# ESP_Thermometer.net
KiCad netlist of a schematic drawn in EAGLE
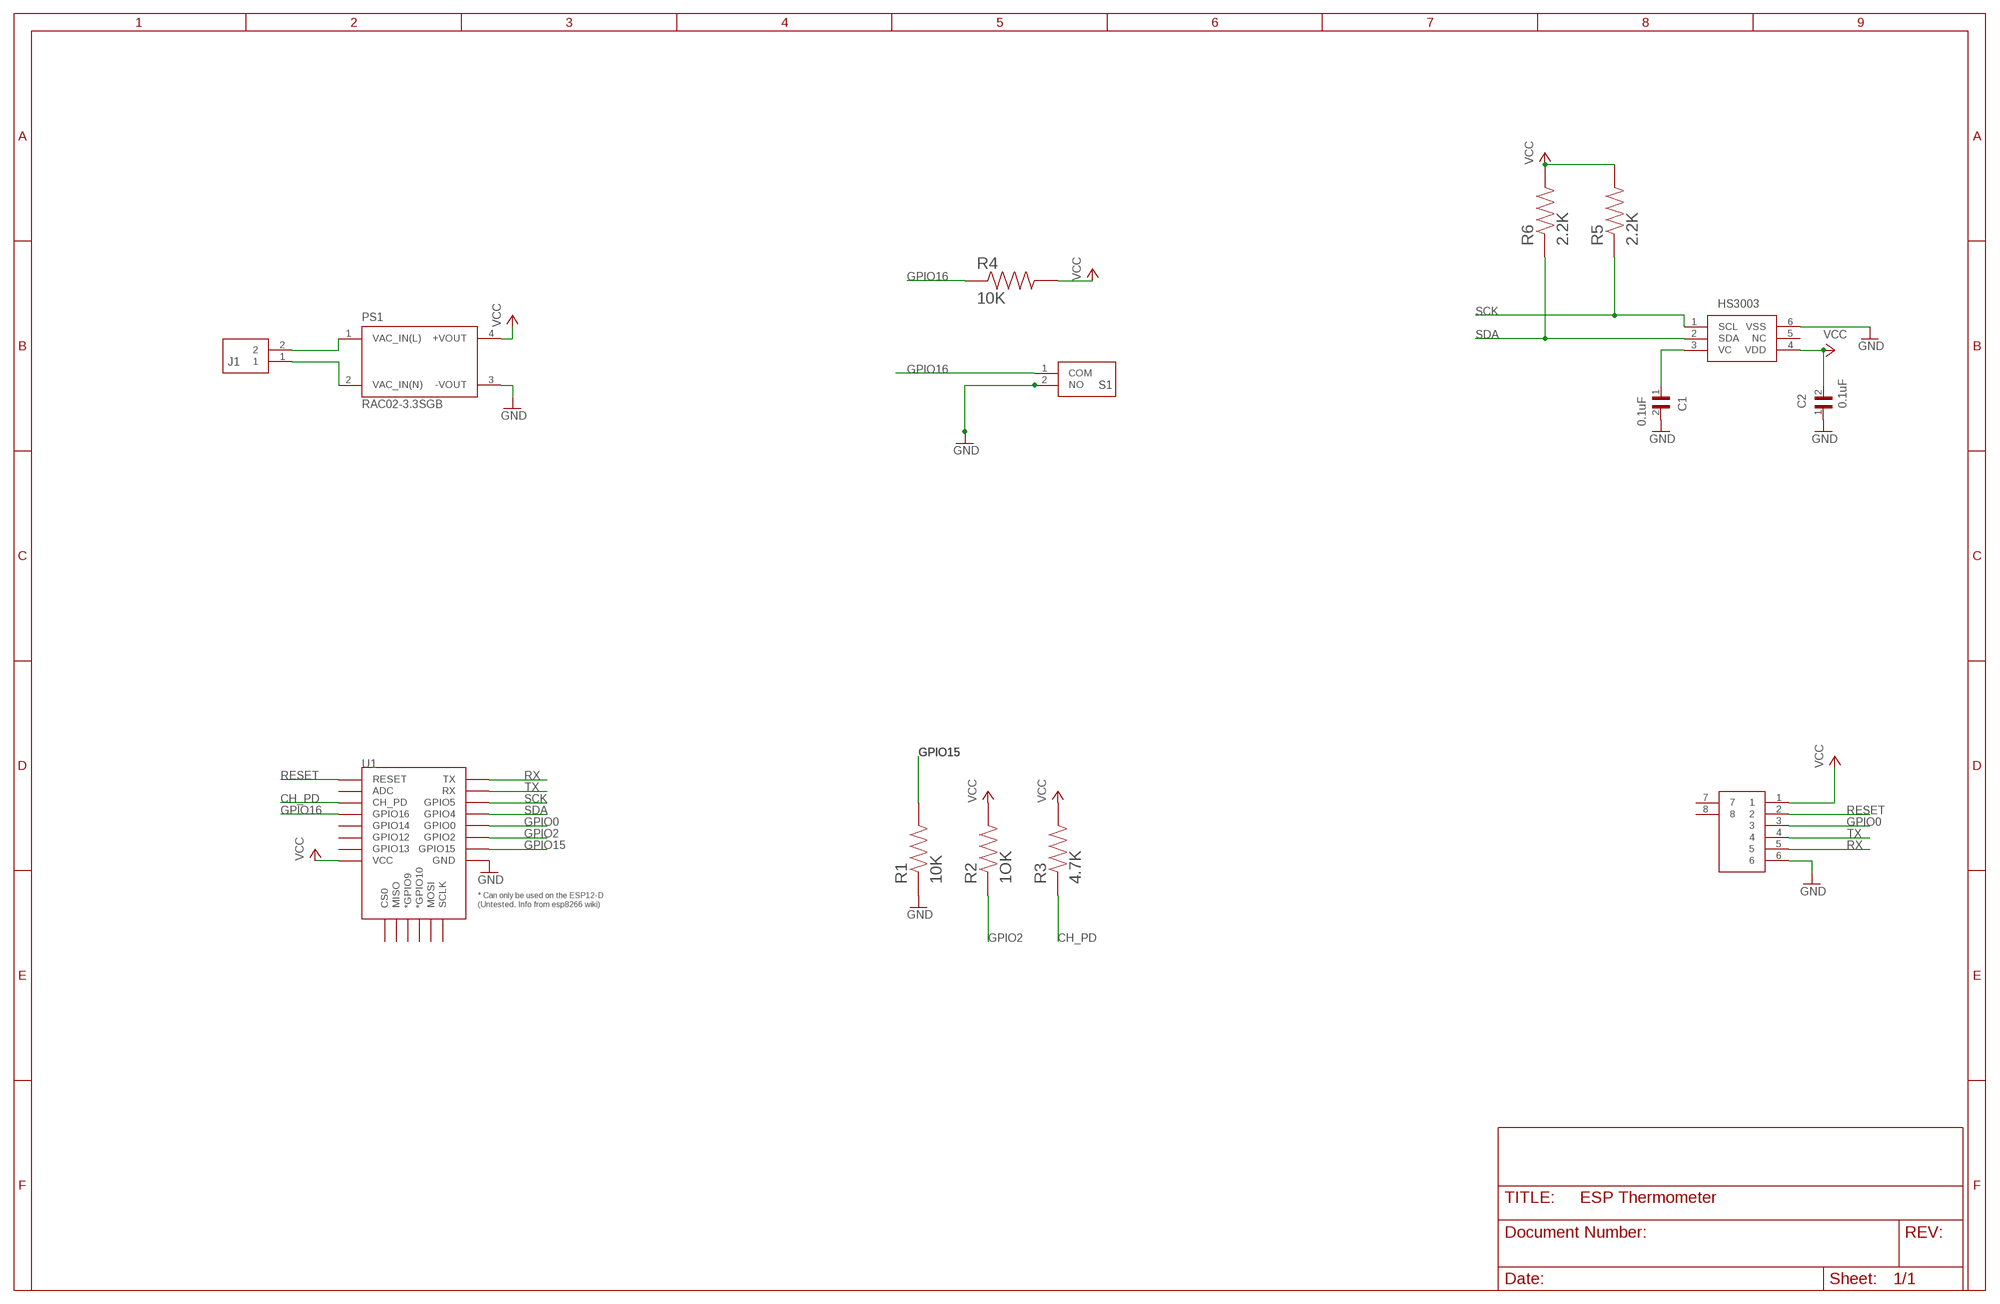
[diagram p0: schematic, sheet 1]

(export (version "E")
  (design (tool "Eeschema 10.0.6"))
  (components
    (comp (ref "C1")
      (value "0.1uF")
      (footprint "eagle-import:CAPC2012X94N")
      (fields (field (name "MF") "AVX") (field (name "MP") "0805YC103J4T2A"))
      (libsource (lib "eagle-import") (part "0805YC103J4T2A"))
    )
    (comp (ref "C2")
      (value "0.1uF")
      (footprint "eagle-import:CAPC2012X94N")
      (fields (field (name "MF") "AVX") (field (name "MP") "0805YC103J4T2A"))
      (libsource (lib "eagle-import") (part "0805YC103J4T2A"))
    )
    (comp (ref "IC1")
      (value "HS3003")
      (footprint "eagle-import:HS3004")
      (fields (field (name "MOUSER_PART_NUMBER") "972-HS3003"))
      (libsource (lib "eagle-import") (part "HS3003"))
    )
    (comp (ref "J1")
      (value "TB006-508-02BE")
      (footprint "eagle-import:TB00650802BE")
      (fields (field (name "MOUSER_PART_NUMBER") "490-TB006-508-02BE"))
      (libsource (lib "eagle-import") (part "TB006-508-02BE"))
    )
    (comp (ref "J2")
      (value "52852-0670")
      (footprint "eagle-import:528520670")
      (fields (field (name "MOUSER_PART_NUMBER") "538-52852-0670"))
      (libsource (lib "eagle-import") (part "52852-0670"))
    )
    (comp (ref "PS1")
      (value "RAC02-3.3SGB")
      (footprint "eagle-import:CONV_RAC02-3.3SGB")
      (fields (field (name "MF") "Recom Power"))
      (libsource (lib "eagle-import") (part "RAC02-3.3SGB"))
    )
    (comp (ref "R1")
      (value "10K")
      (footprint "eagle-import:RESC2012X60N")
      (fields (field (name "MF") "Yageo") (field (name "MP") "RC0805FR-07330RL"))
      (libsource (lib "eagle-import") (part "RC0805FR-07330RL"))
    )
    (comp (ref "R2")
      (value "1OK")
      (footprint "eagle-import:RESC2012X60N")
      (fields (field (name "MF") "Yageo") (field (name "MP") "RC0805FR-07330RL"))
      (libsource (lib "eagle-import") (part "RC0805FR-07330RL"))
    )
    (comp (ref "R3")
      (value "4.7K")
      (footprint "eagle-import:RESC2012X60N")
      (fields (field (name "MF") "Yageo") (field (name "MP") "RC0805FR-07330RL"))
      (libsource (lib "eagle-import") (part "RC0805FR-07330RL"))
    )
    (comp (ref "R4")
      (value "10K")
      (footprint "eagle-import:RESC2012X60N")
      (fields (field (name "MF") "Yageo") (field (name "MP") "RC0805FR-07330RL"))
      (libsource (lib "eagle-import") (part "RC0805FR-07330RL"))
    )
    (comp (ref "R5")
      (value "2.2K")
      (footprint "eagle-import:RESC2012X60N")
      (fields (field (name "MF") "Yageo") (field (name "MP") "RC0805FR-07330RL"))
      (libsource (lib "eagle-import") (part "RC0805FR-07330RL"))
    )
    (comp (ref "R6")
      (value "2.2K")
      (footprint "eagle-import:RESC2012X60N")
      (fields (field (name "MF") "Yageo") (field (name "MP") "RC0805FR-07330RL"))
      (libsource (lib "eagle-import") (part "RC0805FR-07330RL"))
    )
    (comp (ref "S1")
      (value "PTS636_SP50_SMTR_LFS")
      (footprint "eagle-import:PTS636SP50SMTRLFS")
      (fields
        (field (name "MANUFACTURER_PART_NUMBER") "PTS636 SP50 SMTR LFS")
        (field (name "MOUSER_PART_NUMBER") "611-PTS636SP50SMTRLF")
      )
      (libsource (lib "eagle-import") (part "PTS636_SP50_SMTR_LFS"))
    )
    (comp (ref "U1")
      (value "ESP12ESMD")
      (footprint "eagle-import:ESP12E-SMD")
      (libsource (lib "eagle-import") (part "ESP12ESMD"))
    )
  )
  (nets
    (net (code "1") (name "/CH_PD") (class "Default")
      (node (ref "R3") (pin "1") (pinfunction "1_1") (pintype "passive"))
      (node (ref "U1") (pin "CH_PD") (pinfunction "CH_PD_CH_PD") (pintype "bidirectional"))
    )
    (net (code "2") (name "/GPIO0") (class "Default")
      (node (ref "J2") (pin "3") (pinfunction "3_3") (pintype "bidirectional"))
      (node (ref "U1") (pin "GPIO0") (pinfunction "GPIO0_GPIO0") (pintype "bidirectional"))
    )
    (net (code "3") (name "/GPIO2") (class "Default")
      (node (ref "R2") (pin "1") (pinfunction "1_1") (pintype "passive"))
      (node (ref "U1") (pin "GPIO2") (pinfunction "GPIO2_GPIO2") (pintype "bidirectional"))
    )
    (net (code "4") (name "/GPIO15") (class "Default")
      (node (ref "R1") (pin "2") (pinfunction "2_2") (pintype "passive"))
      (node (ref "U1") (pin "GPIO15") (pinfunction "GPIO15_GPIO15") (pintype "bidirectional"))
    )
    (net (code "5") (name "/GPIO16") (class "Default")
      (node (ref "R4") (pin "1") (pinfunction "1_1") (pintype "passive"))
      (node (ref "S1") (pin "1") (pinfunction "COM_1") (pintype "bidirectional"))
      (node (ref "U1") (pin "GPIO16") (pinfunction "GPIO16_GPIO16") (pintype "bidirectional"))
    )
    (net (code "6") (name "/RESET") (class "Default")
      (node (ref "J2") (pin "2") (pinfunction "2_2") (pintype "bidirectional"))
      (node (ref "U1") (pin "RESET") (pinfunction "RESET_RESET") (pintype "bidirectional"))
    )
    (net (code "7") (name "/RX") (class "Default")
      (node (ref "J2") (pin "5") (pinfunction "5_5") (pintype "bidirectional"))
      (node (ref "U1") (pin "TXD0") (pinfunction "TX_TXD0") (pintype "bidirectional"))
    )
    (net (code "8") (name "/SCK") (class "Default")
      (node (ref "IC1") (pin "1") (pinfunction "SCL_1") (pintype "bidirectional"))
      (node (ref "R5") (pin "1") (pinfunction "1_1") (pintype "passive"))
      (node (ref "U1") (pin "GPIO5") (pinfunction "GPIO5_GPIO5") (pintype "bidirectional"))
    )
    (net (code "9") (name "/SDA") (class "Default")
      (node (ref "IC1") (pin "2") (pinfunction "SDA_2") (pintype "bidirectional"))
      (node (ref "R6") (pin "1") (pinfunction "1_1") (pintype "passive"))
      (node (ref "U1") (pin "GPIO4") (pinfunction "GPIO4_GPIO4") (pintype "bidirectional"))
    )
    (net (code "10") (name "/TX") (class "Default")
      (node (ref "J2") (pin "4") (pinfunction "4_4") (pintype "bidirectional"))
      (node (ref "U1") (pin "RXD0") (pinfunction "RX_RXD0") (pintype "bidirectional"))
    )
    (net (code "11") (name "GND") (class "Default")
      (node (ref "C1") (pin "2") (pinfunction "2_2") (pintype "passive"))
      (node (ref "C2") (pin "1") (pinfunction "1_1") (pintype "passive"))
      (node (ref "IC1") (pin "6") (pinfunction "VSS_6") (pintype "bidirectional"))
      (node (ref "J2") (pin "6") (pinfunction "6_6") (pintype "bidirectional"))
      (node (ref "PS1") (pin "3") (pinfunction "-VOUT_3") (pintype "output"))
      (node (ref "R1") (pin "1") (pinfunction "1_1") (pintype "passive"))
      (node (ref "S1") (pin "2") (pinfunction "NO_2") (pintype "bidirectional"))
      (node (ref "U1") (pin "GND") (pinfunction "GND_GND") (pintype "bidirectional"))
    )
    (net (code "12") (name "Net-(IC1-VC)") (class "Default")
      (node (ref "C1") (pin "1") (pinfunction "1_1") (pintype "passive"))
      (node (ref "IC1") (pin "3") (pinfunction "VC_3") (pintype "bidirectional"))
    )
    (net (code "13") (name "Net-(PS1-VAC_IN(L))") (class "Default")
      (node (ref "J1") (pin "2") (pinfunction "2_2") (pintype "bidirectional"))
      (node (ref "PS1") (pin "1") (pinfunction "VAC_IN(L)_1") (pintype "input"))
    )
    (net (code "14") (name "Net-(PS1-VAC_IN(N))") (class "Default")
      (node (ref "J1") (pin "1") (pinfunction "1_1") (pintype "bidirectional"))
      (node (ref "PS1") (pin "2") (pinfunction "VAC_IN(N)_2") (pintype "input"))
    )
    (net (code "15") (name "VCC") (class "Default")
      (node (ref "C2") (pin "2") (pinfunction "2_2") (pintype "passive"))
      (node (ref "IC1") (pin "4") (pinfunction "VDD_4") (pintype "bidirectional"))
      (node (ref "J2") (pin "1") (pinfunction "1_1") (pintype "bidirectional"))
      (node (ref "PS1") (pin "4") (pinfunction "+VOUT_4") (pintype "output"))
      (node (ref "R2") (pin "2") (pinfunction "2_2") (pintype "passive"))
      (node (ref "R3") (pin "2") (pinfunction "2_2") (pintype "passive"))
      (node (ref "R4") (pin "2") (pinfunction "2_2") (pintype "passive"))
      (node (ref "R5") (pin "2") (pinfunction "2_2") (pintype "passive"))
      (node (ref "R6") (pin "2") (pinfunction "2_2") (pintype "passive"))
      (node (ref "U1") (pin "VCC") (pinfunction "VCC_VCC") (pintype "bidirectional"))
    )
    (net (code "16") (name "unconnected-(IC1-NC-Pad5)") (class "Default")
      (node (ref "IC1") (pin "5") (pinfunction "NC_5") (pintype "no_connect"))
    )
    (net (code "17") (name "unconnected-(J2-Pad7)") (class "Default")
      (node (ref "J2") (pin "7") (pinfunction "7_7") (pintype "bidirectional"))
    )
    (net (code "18") (name "unconnected-(J2-Pad8)") (class "Default")
      (node (ref "J2") (pin "8") (pinfunction "8_8") (pintype "bidirectional"))
    )
    (net (code "19") (name "unconnected-(U1-*GPIO9-PadGPIO9)") (class "Default")
      (node (ref "U1") (pin "GPIO9") (pinfunction "*GPIO9_GPIO9") (pintype "bidirectional"))
    )
    (net (code "20") (name "unconnected-(U1-*GPIO10-PadGPIO10)") (class "Default")
      (node (ref "U1") (pin "GPIO10") (pinfunction "*GPIO10_GPIO10") (pintype "bidirectional"))
    )
    (net (code "21") (name "unconnected-(U1-PadADC)") (class "Default")
      (node (ref "U1") (pin "ADC") (pinfunction "ADC_ADC") (pintype "bidirectional"))
    )
    (net (code "22") (name "unconnected-(U1-PadCS0)") (class "Default")
      (node (ref "U1") (pin "CS0") (pinfunction "CS0_CS0") (pintype "bidirectional"))
    )
    (net (code "23") (name "unconnected-(U1-PadGPIO12)") (class "Default")
      (node (ref "U1") (pin "GPIO12") (pinfunction "GPIO12_GPIO12") (pintype "bidirectional"))
    )
    (net (code "24") (name "unconnected-(U1-PadGPIO13)") (class "Default")
      (node (ref "U1") (pin "GPIO13") (pinfunction "GPIO13_GPIO13") (pintype "bidirectional"))
    )
    (net (code "25") (name "unconnected-(U1-PadGPIO14)") (class "Default")
      (node (ref "U1") (pin "GPIO14") (pinfunction "GPIO14_GPIO14") (pintype "bidirectional"))
    )
    (net (code "26") (name "unconnected-(U1-PadMISO)") (class "Default")
      (node (ref "U1") (pin "MISO") (pinfunction "MISO_MISO") (pintype "bidirectional"))
    )
    (net (code "27") (name "unconnected-(U1-PadMOSI)") (class "Default")
      (node (ref "U1") (pin "MOSI") (pinfunction "MOSI_MOSI") (pintype "bidirectional"))
    )
    (net (code "28") (name "unconnected-(U1-PadSCLK)") (class "Default")
      (node (ref "U1") (pin "SCLK") (pinfunction "SCLK_SCLK") (pintype "bidirectional"))
    )
  )
)
